# Backlight.net
KiCad netlist of a schematic drawn in EAGLE
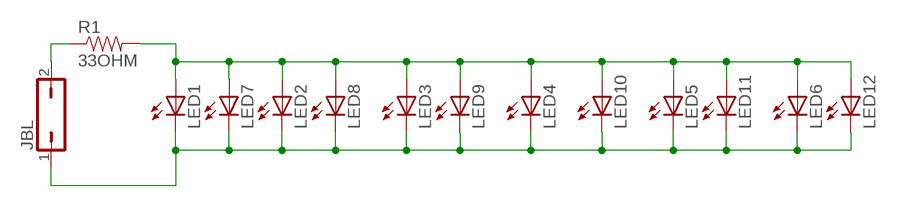
[diagram p0: schematic, sheet 1]

(export (version "E")
  (design (tool "Eeschema 10.0.6"))
  (components
    (comp (ref "JBL")
      (value "JP1Q")
      (footprint "eagle-import:JP1")
      (libsource (lib "eagle-import") (part "JP1Q"))
    )
    (comp (ref "LED1")
      (value "LEDCHIP-LED0603")
      (footprint "eagle-import:CHIP-LED0603")
      (libsource (lib "eagle-import") (part "LEDCHIP-LED0603"))
    )
    (comp (ref "LED2")
      (value "LEDCHIP-LED0603")
      (footprint "eagle-import:CHIP-LED0603")
      (libsource (lib "eagle-import") (part "LEDCHIP-LED0603"))
    )
    (comp (ref "LED3")
      (value "LEDCHIP-LED0603")
      (footprint "eagle-import:CHIP-LED0603")
      (libsource (lib "eagle-import") (part "LEDCHIP-LED0603"))
    )
    (comp (ref "LED4")
      (value "LEDCHIP-LED0603")
      (footprint "eagle-import:CHIP-LED0603")
      (libsource (lib "eagle-import") (part "LEDCHIP-LED0603"))
    )
    (comp (ref "LED5")
      (value "LEDCHIP-LED0603")
      (footprint "eagle-import:CHIP-LED0603")
      (libsource (lib "eagle-import") (part "LEDCHIP-LED0603"))
    )
    (comp (ref "LED6")
      (value "LEDCHIP-LED0603")
      (footprint "eagle-import:CHIP-LED0603")
      (libsource (lib "eagle-import") (part "LEDCHIP-LED0603"))
    )
    (comp (ref "LED7")
      (value "LEDCHIP-LED0603")
      (footprint "eagle-import:CHIP-LED0603")
      (libsource (lib "eagle-import") (part "LEDCHIP-LED0603"))
    )
    (comp (ref "LED8")
      (value "LEDCHIP-LED0603")
      (footprint "eagle-import:CHIP-LED0603")
      (libsource (lib "eagle-import") (part "LEDCHIP-LED0603"))
    )
    (comp (ref "LED9")
      (value "LEDCHIP-LED0603")
      (footprint "eagle-import:CHIP-LED0603")
      (libsource (lib "eagle-import") (part "LEDCHIP-LED0603"))
    )
    (comp (ref "LED10")
      (value "LEDCHIP-LED0603")
      (footprint "eagle-import:CHIP-LED0603")
      (libsource (lib "eagle-import") (part "LEDCHIP-LED0603"))
    )
    (comp (ref "LED11")
      (value "LEDCHIP-LED0603")
      (footprint "eagle-import:CHIP-LED0603")
      (libsource (lib "eagle-import") (part "LEDCHIP-LED0603"))
    )
    (comp (ref "LED12")
      (value "LEDCHIP-LED0603")
      (footprint "eagle-import:CHIP-LED0603")
      (libsource (lib "eagle-import") (part "LEDCHIP-LED0603"))
    )
    (comp (ref "R1")
      (value "33OHM")
      (footprint "eagle-import:0603")
      (libsource (lib "eagle-import") (part "33OHM1/10W1%(0603)"))
    )
  )
  (nets
    (net (code "1") (name "Net-(JBL-Pad1)") (class "Default")
      (node (ref "JBL") (pin "1") (pinfunction "1_1") (pintype "passive"))
      (node (ref "LED1") (pin "C") (pinfunction "C_C") (pintype "passive"))
      (node (ref "LED10") (pin "C") (pinfunction "C_C") (pintype "passive"))
      (node (ref "LED11") (pin "C") (pinfunction "C_C") (pintype "passive"))
      (node (ref "LED12") (pin "C") (pinfunction "C_C") (pintype "passive"))
      (node (ref "LED2") (pin "C") (pinfunction "C_C") (pintype "passive"))
      (node (ref "LED3") (pin "C") (pinfunction "C_C") (pintype "passive"))
      (node (ref "LED4") (pin "C") (pinfunction "C_C") (pintype "passive"))
      (node (ref "LED5") (pin "C") (pinfunction "C_C") (pintype "passive"))
      (node (ref "LED6") (pin "C") (pinfunction "C_C") (pintype "passive"))
      (node (ref "LED7") (pin "C") (pinfunction "C_C") (pintype "passive"))
      (node (ref "LED8") (pin "C") (pinfunction "C_C") (pintype "passive"))
      (node (ref "LED9") (pin "C") (pinfunction "C_C") (pintype "passive"))
    )
    (net (code "2") (name "Net-(JBL-Pad2)") (class "Default")
      (node (ref "JBL") (pin "2") (pinfunction "2_2") (pintype "passive"))
      (node (ref "R1") (pin "1") (pinfunction "1_1") (pintype "passive"))
    )
    (net (code "3") (name "Net-(LED1-PadA)") (class "Default")
      (node (ref "LED1") (pin "A") (pinfunction "A_A") (pintype "passive"))
      (node (ref "LED10") (pin "A") (pinfunction "A_A") (pintype "passive"))
      (node (ref "LED11") (pin "A") (pinfunction "A_A") (pintype "passive"))
      (node (ref "LED12") (pin "A") (pinfunction "A_A") (pintype "passive"))
      (node (ref "LED2") (pin "A") (pinfunction "A_A") (pintype "passive"))
      (node (ref "LED3") (pin "A") (pinfunction "A_A") (pintype "passive"))
      (node (ref "LED4") (pin "A") (pinfunction "A_A") (pintype "passive"))
      (node (ref "LED5") (pin "A") (pinfunction "A_A") (pintype "passive"))
      (node (ref "LED6") (pin "A") (pinfunction "A_A") (pintype "passive"))
      (node (ref "LED7") (pin "A") (pinfunction "A_A") (pintype "passive"))
      (node (ref "LED8") (pin "A") (pinfunction "A_A") (pintype "passive"))
      (node (ref "LED9") (pin "A") (pinfunction "A_A") (pintype "passive"))
      (node (ref "R1") (pin "2") (pinfunction "2_2") (pintype "passive"))
    )
  )
)
